# AS5600.net
KiCad netlist of a schematic drawn in Altium Designer
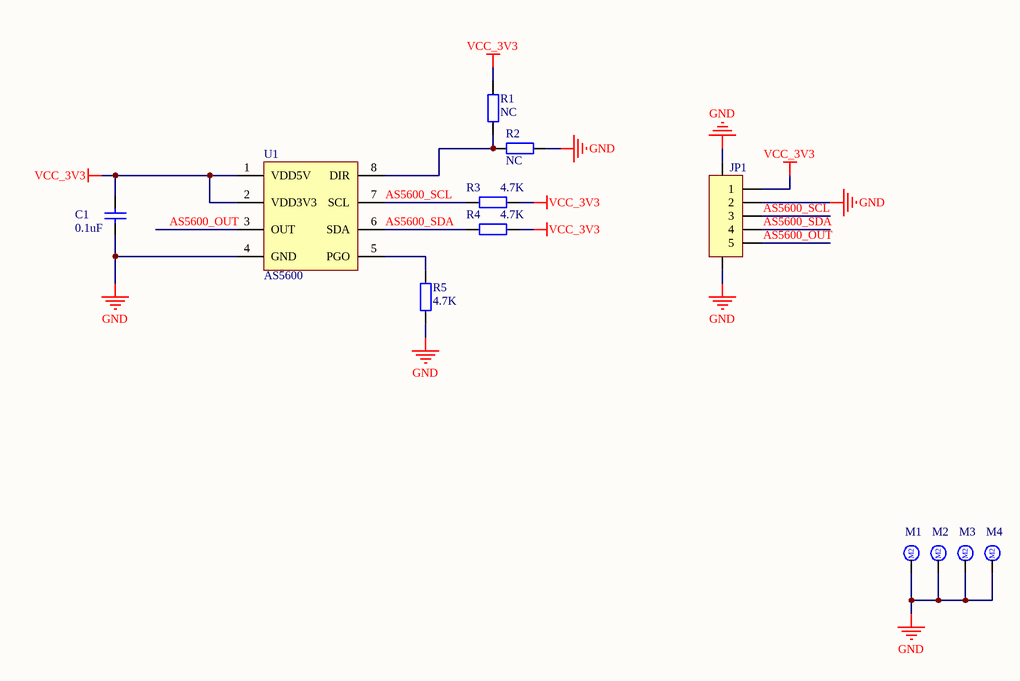
[diagram p0: AS5600.SchDoc]

(export (version "E")
  (design (tool "Eeschema 10.0.6"))
  (components
    (comp (ref "C1")
      (value "0.1uF")
      (footprint "C0402_L")
      (description "贴片电容")
      (libsource (lib "0.1 - 电阻-电容-电感-晶振-晶体-磁珠-电位器") (part "C"))
    )
    (comp (ref "JP1")
      (value "CON-5P")
      (footprint "SH1.0-WT-5P")
      (description "5P连接器")
      (libsource (lib "5.0 - 1.00mm连接器(FPC1.0-SH1.0)") (part "Header 5"))
    )
    (comp (ref "M1")
      (value "M2.5")
      (footprint "M2焊盘")
      (description "M2孔支撑柱")
      (libsource (lib "USER_Lib") (part "M2系列"))
    )
    (comp (ref "M2")
      (value "M2.5")
      (footprint "M2焊盘")
      (description "M2孔支撑柱")
      (libsource (lib "USER_Lib") (part "M2系列"))
    )
    (comp (ref "M3")
      (value "M2.5")
      (footprint "M2焊盘")
      (description "M2孔支撑柱")
      (libsource (lib "USER_Lib") (part "M2系列"))
    )
    (comp (ref "M4")
      (value "M2.5")
      (footprint "M2焊盘")
      (description "M2孔支撑柱")
      (libsource (lib "USER_Lib") (part "M2系列"))
    )
    (comp (ref "R1")
      (value "NC")
      (footprint "R0402_L")
      (description "贴片电阻")
      (libsource (lib "0.1 - 电阻-电容-电感-晶振-晶体-磁珠-电位器") (part "R"))
    )
    (comp (ref "R2")
      (value "NC")
      (footprint "R0402_L")
      (description "贴片电阻")
      (libsource (lib "0.1 - 电阻-电容-电感-晶振-晶体-磁珠-电位器") (part "R"))
    )
    (comp (ref "R3")
      (value "4.7K")
      (footprint "R0402_L")
      (description "贴片电阻")
      (libsource (lib "0.1 - 电阻-电容-电感-晶振-晶体-磁珠-电位器") (part "R"))
    )
    (comp (ref "R4")
      (value "4.7K")
      (footprint "R0402_L")
      (description "贴片电阻")
      (libsource (lib "0.1 - 电阻-电容-电感-晶振-晶体-磁珠-电位器") (part "R"))
    )
    (comp (ref "R5")
      (value "4.7K")
      (footprint "R0402_L")
      (description "贴片电阻")
      (libsource (lib "0.1 - 电阻-电容-电感-晶振-晶体-磁珠-电位器") (part "R"))
    )
    (comp (ref "U1")
      (value "AS5600")
      (footprint "SOIC-8L")
      (description "12bit 磁编码器")
      (libsource (lib "USER_Lib") (part "AS5600"))
    )
  )
  (nets
    (net (code "1") (name "/AS5600_OUT") (class "Default")
      (node (ref "JP1") (pin "5") (pinfunction "5_5") (pintype "passive"))
      (node (ref "U1") (pin "3") (pinfunction "OUT_3") (pintype "passive"))
    )
    (net (code "2") (name "/AS5600_SCL") (class "Default")
      (node (ref "JP1") (pin "3") (pinfunction "3_3") (pintype "passive"))
      (node (ref "R3") (pin "2") (pinfunction "2_2") (pintype "passive"))
      (node (ref "U1") (pin "7") (pinfunction "SCL_7") (pintype "passive"))
    )
    (net (code "3") (name "/AS5600_SDA") (class "Default")
      (node (ref "JP1") (pin "4") (pinfunction "4_4") (pintype "passive"))
      (node (ref "R4") (pin "2") (pinfunction "2_2") (pintype "passive"))
      (node (ref "U1") (pin "6") (pinfunction "SDA_6") (pintype "passive"))
    )
    (net (code "4") (name "GND") (class "Default")
      (node (ref "C1") (pin "1") (pinfunction "1_1") (pintype "passive"))
      (node (ref "JP1") (pin "0") (pinfunction "0_0") (pintype "passive"))
      (node (ref "JP1") (pin "2") (pinfunction "2_2") (pintype "passive"))
      (node (ref "M1") (pin "1") (pinfunction "1_1") (pintype "passive"))
      (node (ref "M2") (pin "1") (pinfunction "1_1") (pintype "passive"))
      (node (ref "M3") (pin "1") (pinfunction "1_1") (pintype "passive"))
      (node (ref "M4") (pin "1") (pinfunction "1_1") (pintype "passive"))
      (node (ref "R2") (pin "1") (pinfunction "1_1") (pintype "passive"))
      (node (ref "R5") (pin "2") (pinfunction "2_2") (pintype "passive"))
      (node (ref "U1") (pin "4") (pinfunction "GND_4") (pintype "passive"))
    )
    (net (code "5") (name "Net-(U1-DIR)") (class "Default")
      (node (ref "R1") (pin "1") (pinfunction "1_1") (pintype "passive"))
      (node (ref "R2") (pin "2") (pinfunction "2_2") (pintype "passive"))
      (node (ref "U1") (pin "8") (pinfunction "DIR_8") (pintype "passive"))
    )
    (net (code "6") (name "Net-(U1-PGO)") (class "Default")
      (node (ref "R5") (pin "1") (pinfunction "1_1") (pintype "passive"))
      (node (ref "U1") (pin "5") (pinfunction "PGO_5") (pintype "passive"))
    )
    (net (code "7") (name "VCC_3V3") (class "Default")
      (node (ref "C1") (pin "2") (pinfunction "2_2") (pintype "passive"))
      (node (ref "JP1") (pin "1") (pinfunction "1_1") (pintype "passive"))
      (node (ref "R1") (pin "2") (pinfunction "2_2") (pintype "passive"))
      (node (ref "R3") (pin "1") (pinfunction "1_1") (pintype "passive"))
      (node (ref "R4") (pin "1") (pinfunction "1_1") (pintype "passive"))
      (node (ref "U1") (pin "1") (pinfunction "VDD5V_1") (pintype "passive"))
      (node (ref "U1") (pin "2") (pinfunction "VDD3V3_2") (pintype "passive"))
    )
  )
)
